# Bus_Terminal.net
KiCad netlist of a schematic drawn in Altium Designer
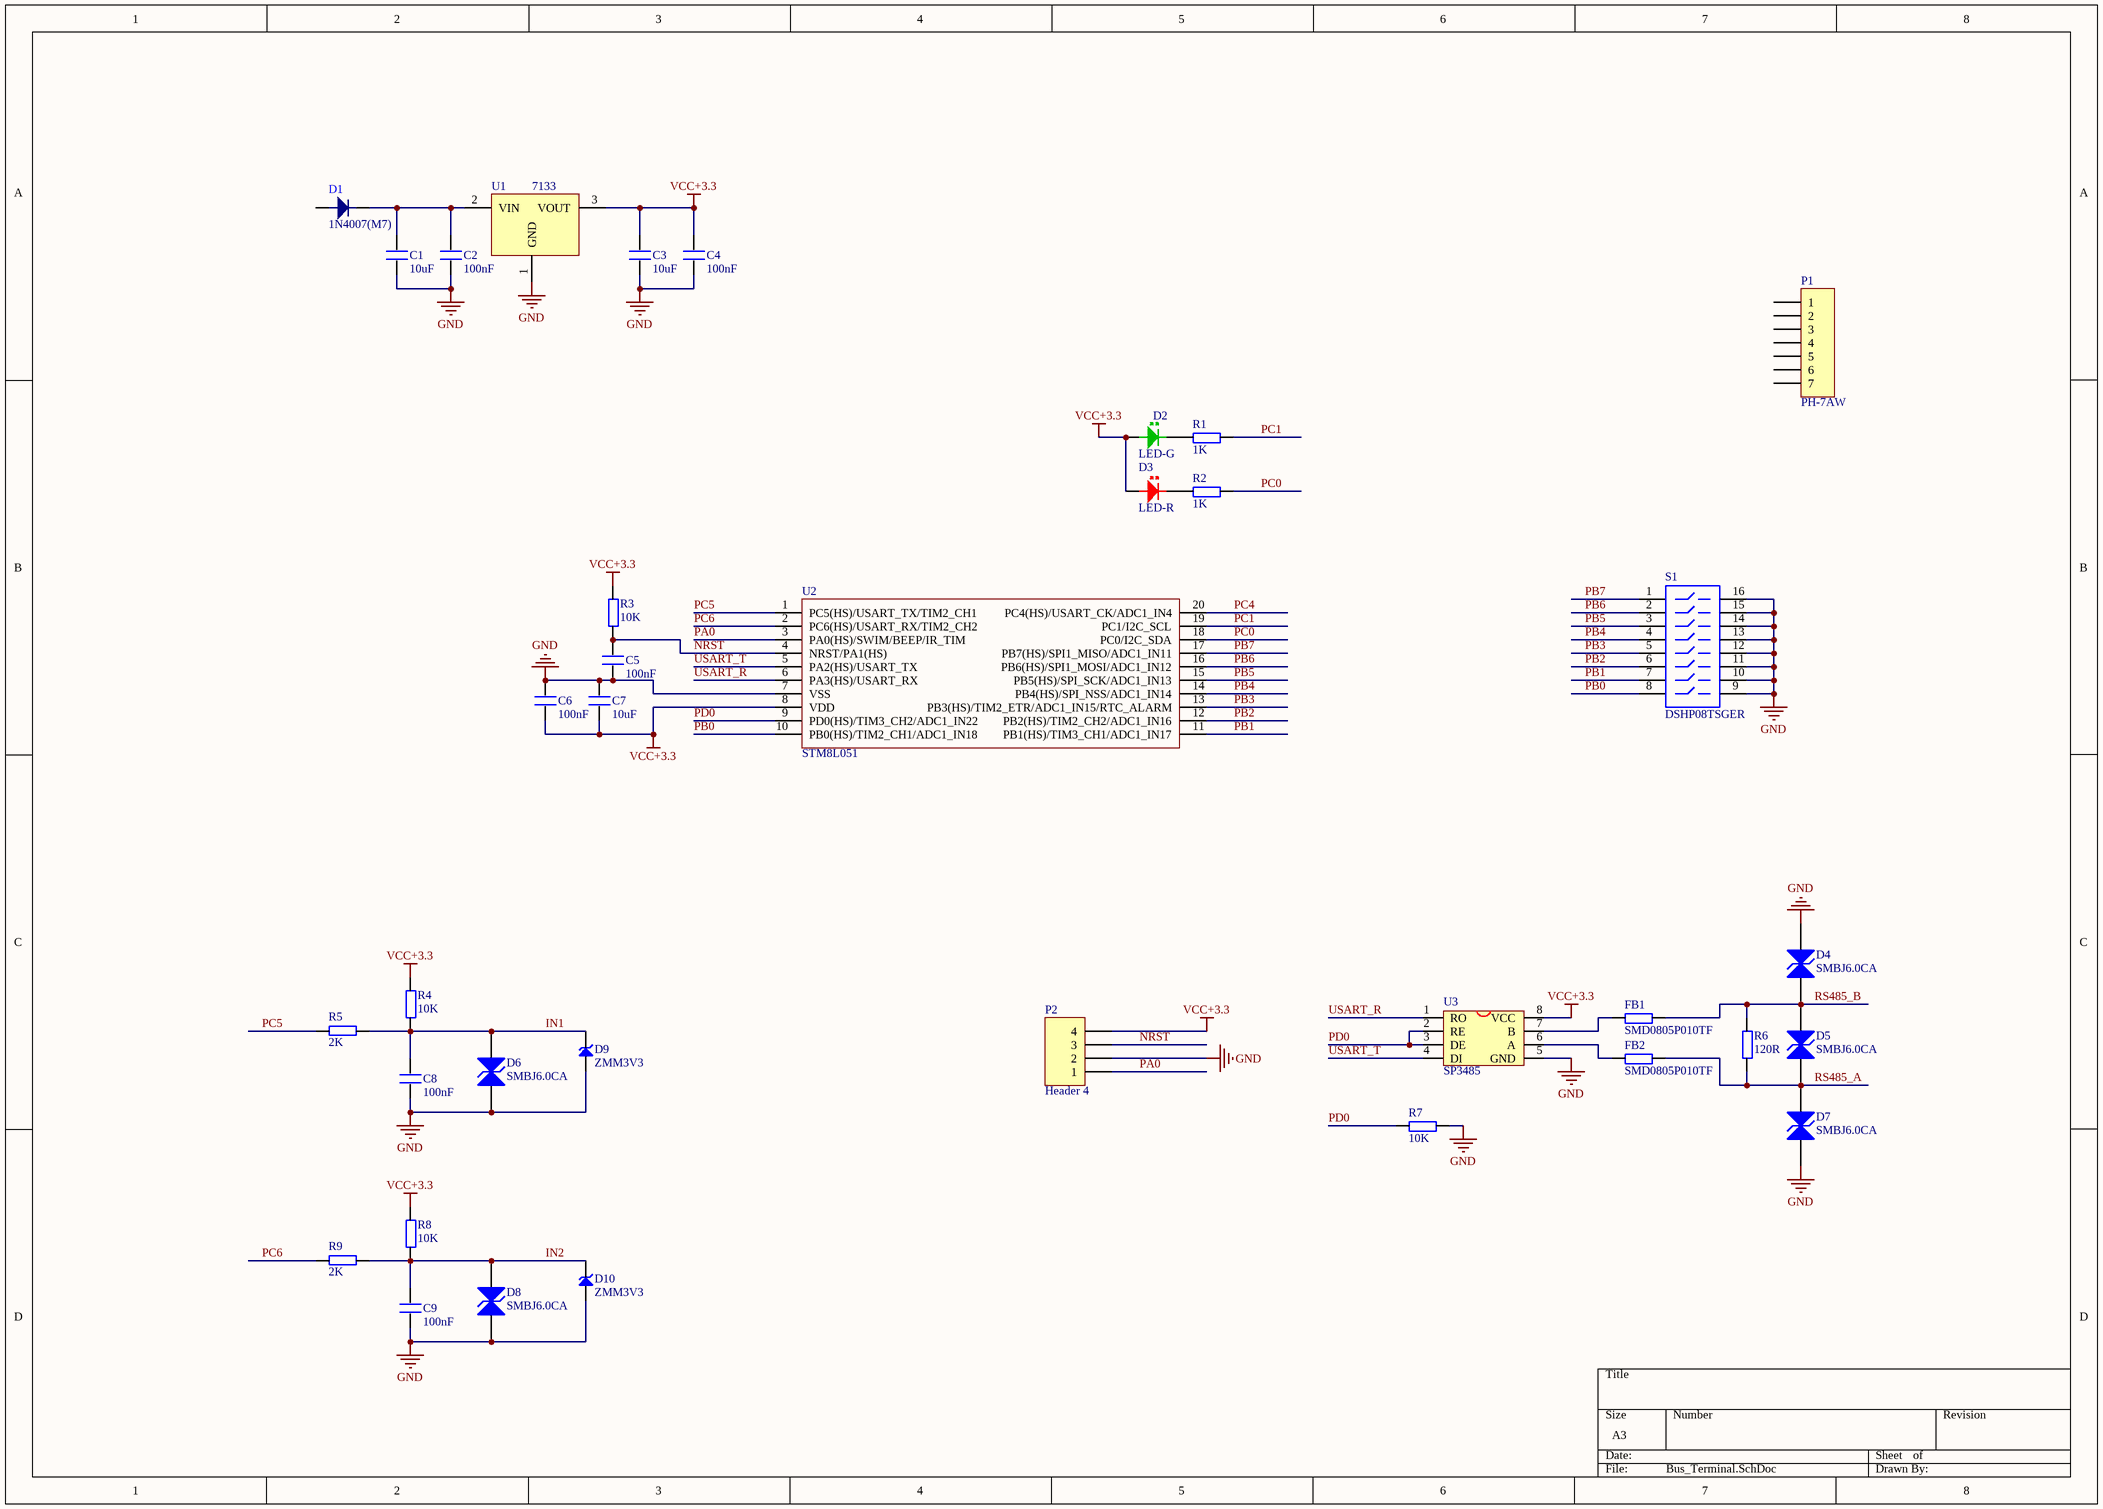
[diagram p0: Bus_Terminal.SchDoc]

(export (version "E")
  (design (tool "Eeschema 10.0.6"))
  (components
    (comp (ref "C1") (value "10uF") (footprint "0805-C") (libsource (lib "mylib") (part "C")))
    (comp (ref "C2") (value "100nF") (footprint "0603-C") (libsource (lib "mylib") (part "C")))
    (comp (ref "C3") (value "10uF") (footprint "0805-C") (libsource (lib "mylib") (part "C")))
    (comp (ref "C4") (value "100nF") (footprint "0603-C") (libsource (lib "mylib") (part "C")))
    (comp (ref "C5") (value "100nF") (footprint "0603-C") (libsource (lib "mylib") (part "C")))
    (comp (ref "C6") (value "100nF") (footprint "0603-C") (libsource (lib "mylib") (part "C")))
    (comp (ref "C7") (value "10uF") (footprint "0805-C") (libsource (lib "mylib") (part "C")))
    (comp (ref "C8") (value "100nF") (footprint "0603-C") (libsource (lib "mylib") (part "C")))
    (comp (ref "C9") (value "100nF") (footprint "0603-C") (libsource (lib "mylib") (part "C")))
    (comp (ref "D1")
      (value "1N4007(M7)")
      (footprint "DO-214AC(SMA)")
      (description "1A整流二极管")
      (libsource (lib "mylib") (part "1N4007"))
    )
    (comp (ref "D2")
      (value "LED-G")
      (footprint "0805-LED")
      (description "绿色LED")
      (libsource (lib "mylib") (part "LED-GRE"))
    )
    (comp (ref "D3")
      (value "LED-R")
      (footprint "0805-LED")
      (description "红色LED")
      (libsource (lib "mylib") (part "LED-RED"))
    )
    (comp (ref "D4")
      (value "SMBJ6.0CA")
      (footprint "SMB-DO-214AA-CA")
      (description "TVS")
      (libsource (lib "mylib") (part "SMBJ6.0CA"))
    )
    (comp (ref "D5")
      (value "SMBJ6.0CA")
      (footprint "SMB-DO-214AA-CA")
      (description "TVS")
      (libsource (lib "mylib") (part "SMBJ6.0CA"))
    )
    (comp (ref "D6")
      (value "SMBJ6.0CA")
      (footprint "SMB-DO-214AA-CA")
      (description "TVS")
      (libsource (lib "mylib") (part "SMBJ6.0CA"))
    )
    (comp (ref "D7")
      (value "SMBJ6.0CA")
      (footprint "SMB-DO-214AA-CA")
      (description "TVS")
      (libsource (lib "mylib") (part "SMBJ6.0CA"))
    )
    (comp (ref "D8")
      (value "SMBJ6.0CA")
      (footprint "SMB-DO-214AA-CA")
      (description "TVS")
      (libsource (lib "mylib") (part "SMBJ6.0CA"))
    )
    (comp (ref "D9") (value "ZMM3V3") (footprint "DIODE_ZMMx") (libsource (lib "mylib") (part "ZMM3V6")))
    (comp (ref "D10") (value "ZMM3V3") (footprint "DIODE_ZMMx") (libsource (lib "mylib") (part "ZMM3V6")))
    (comp (ref "FB1")
      (value "SMD0805P010TF")
      (footprint "0805-R")
      (description "保险丝")
      (libsource (lib "mylib") (part "Res"))
    )
    (comp (ref "FB2")
      (value "SMD0805P010TF")
      (footprint "0805-R")
      (description "保险丝")
      (libsource (lib "mylib") (part "Res"))
    )
    (comp (ref "P1")
      (value "PH-7AW")
      (footprint "PH-7AW")
      (description "连接器")
      (libsource (lib "mylib") (part "PH-7AW"))
    )
    (comp (ref "P2")
      (value "Header 4")
      (footprint "HDR1X4")
      (description "Header, 4-Pin")
      (fields (field (name "PUBLISHER") "Altium Limited"))
      (libsource (lib "mylib") (part "Header 4"))
    )
    (comp (ref "R1") (value "1K") (footprint "0603-R") (libsource (lib "mylib") (part "Res")))
    (comp (ref "R2") (value "1K") (footprint "0603-R") (libsource (lib "mylib") (part "Res")))
    (comp (ref "R3") (value "10K") (footprint "0603-R") (libsource (lib "mylib") (part "Res")))
    (comp (ref "R4") (value "10K") (footprint "0603-R") (libsource (lib "mylib") (part "Res")))
    (comp (ref "R5") (value "2K") (footprint "0603-R") (libsource (lib "mylib") (part "Res")))
    (comp (ref "R6") (value "120R") (footprint "0603-R") (libsource (lib "mylib") (part "Res")))
    (comp (ref "R7") (value "10K") (footprint "0603-R") (libsource (lib "mylib") (part "Res")))
    (comp (ref "R8") (value "10K") (footprint "0603-R") (libsource (lib "mylib") (part "Res")))
    (comp (ref "R9") (value "2K") (footprint "0603-R") (libsource (lib "mylib") (part "Res")))
    (comp (ref "S1")
      (value "DSHP08TSGER")
      (footprint "SOP127P890X230-16N")
      (description "贴片拨码开关")
      (libsource (lib "mylib") (part "DSHP08TSGER"))
    )
    (comp (ref "U1")
      (value "7133")
      (footprint "SOT-89")
      (description "LDO")
      (libsource (lib "mylib") (part "7133"))
    )
    (comp (ref "U2")
      (value "STM8L051")
      (footprint "TSSOP20")
      (description "单片机")
      (libsource (lib "mylib") (part "STM8L051"))
    )
    (comp (ref "U3") (value "SP3485") (footprint "SOP-8") (libsource (lib "mylib") (part "MAX3485")))
  )
  (nets
    (net (code "1") (name "/IN1") (class "Default")
      (node (ref "C8") (pin "2") (pintype "passive"))
      (node (ref "D6") (pin "2") (pinfunction "2_2") (pintype "passive"))
      (node (ref "D9") (pin "2") (pintype "passive"))
      (node (ref "R4") (pin "1") (pintype "passive"))
      (node (ref "R5") (pin "1") (pintype "passive"))
    )
    (net (code "2") (name "/IN2") (class "Default")
      (node (ref "C9") (pin "2") (pintype "passive"))
      (node (ref "D10") (pin "2") (pintype "passive"))
      (node (ref "D8") (pin "2") (pinfunction "2_2") (pintype "passive"))
      (node (ref "R8") (pin "1") (pintype "passive"))
      (node (ref "R9") (pin "1") (pintype "passive"))
    )
    (net (code "3") (name "/NRST") (class "Default")
      (node (ref "C5") (pin "2") (pintype "passive"))
      (node (ref "P2") (pin "3") (pinfunction "3_3") (pintype "passive"))
      (node (ref "R3") (pin "1") (pintype "passive"))
      (node (ref "U2") (pin "4") (pinfunction "NRST/PA1(HS)_4") (pintype "passive"))
    )
    (net (code "4") (name "/PA0") (class "Default")
      (node (ref "P2") (pin "1") (pinfunction "1_1") (pintype "passive"))
      (node (ref "U2") (pin "3") (pinfunction "PA0(HS)/SWIM/BEEP/IR_TIM_3") (pintype "passive"))
    )
    (net (code "5") (name "/PB0") (class "Default")
      (node (ref "S1") (pin "8") (pinfunction "8_8") (pintype "passive"))
      (node (ref "U2") (pin "10") (pinfunction "PB0(HS)/TIM2_CH1/ADC1_IN18_10") (pintype "passive"))
    )
    (net (code "6") (name "/PB1") (class "Default")
      (node (ref "S1") (pin "7") (pinfunction "7_7") (pintype "passive"))
      (node (ref "U2") (pin "11") (pinfunction "PB1(HS)/TIM3_CH1/ADC1_IN17_11") (pintype "passive"))
    )
    (net (code "7") (name "/PB2") (class "Default")
      (node (ref "S1") (pin "6") (pinfunction "6_6") (pintype "passive"))
      (node (ref "U2") (pin "12") (pinfunction "PB2(HS)/TIM2_CH2/ADC1_IN16_12") (pintype "passive"))
    )
    (net (code "8") (name "/PB3") (class "Default")
      (node (ref "S1") (pin "5") (pinfunction "5_5") (pintype "passive"))
      (node (ref "U2") (pin "13") (pinfunction "PB3(HS)/TIM2_ETR/ADC1_IN15/RTC_ALARM_13") (pintype "passive"))
    )
    (net (code "9") (name "/PB4") (class "Default")
      (node (ref "S1") (pin "4") (pinfunction "4_4") (pintype "passive"))
      (node (ref "U2") (pin "14") (pinfunction "PB4(HS)/SPI_NSS/ADC1_IN14_14") (pintype "passive"))
    )
    (net (code "10") (name "/PB5") (class "Default")
      (node (ref "S1") (pin "3") (pinfunction "3_3") (pintype "passive"))
      (node (ref "U2") (pin "15") (pinfunction "PB5(HS)/SPI_SCK/ADC1_IN13_15") (pintype "passive"))
    )
    (net (code "11") (name "/PB6") (class "Default")
      (node (ref "S1") (pin "2") (pinfunction "2_2") (pintype "passive"))
      (node (ref "U2") (pin "16") (pinfunction "PB6(HS)/SPI1_MOSI/ADC1_IN12_16") (pintype "passive"))
    )
    (net (code "12") (name "/PB7") (class "Default")
      (node (ref "S1") (pin "1") (pinfunction "1_1") (pintype "passive"))
      (node (ref "U2") (pin "17") (pinfunction "PB7(HS)/SPI1_MISO/ADC1_IN11_17") (pintype "passive"))
    )
    (net (code "13") (name "/PC0") (class "Default")
      (node (ref "R2") (pin "2") (pintype "passive"))
      (node (ref "U2") (pin "18") (pinfunction "PC0/I2C_SDA_18") (pintype "passive"))
    )
    (net (code "14") (name "/PC1") (class "Default")
      (node (ref "R1") (pin "2") (pintype "passive"))
      (node (ref "U2") (pin "19") (pinfunction "PC1/I2C_SCL_19") (pintype "passive"))
    )
    (net (code "15") (name "/PC4") (class "Default")
      (node (ref "U2") (pin "20") (pinfunction "PC4(HS)/USART_CK/ADC1_IN4_20") (pintype "passive"))
    )
    (net (code "16") (name "/PC5") (class "Default")
      (node (ref "R5") (pin "2") (pintype "passive"))
      (node (ref "U2") (pin "1") (pinfunction "PC5(HS)/USART_TX/TIM2_CH1_1") (pintype "passive"))
    )
    (net (code "17") (name "/PC6") (class "Default")
      (node (ref "R9") (pin "2") (pintype "passive"))
      (node (ref "U2") (pin "2") (pinfunction "PC6(HS)/USART_RX/TIM2_CH2_2") (pintype "passive"))
    )
    (net (code "18") (name "/PD0") (class "Default")
      (node (ref "R7") (pin "1") (pintype "passive"))
      (node (ref "U2") (pin "9") (pinfunction "PD0(HS)/TIM3_CH2/ADC1_IN22_9") (pintype "passive"))
      (node (ref "U3") (pin "2") (pinfunction "RE_2") (pintype "passive"))
      (node (ref "U3") (pin "3") (pinfunction "DE_3") (pintype "passive"))
    )
    (net (code "19") (name "/RS485_A") (class "Default")
      (node (ref "D5") (pin "1") (pinfunction "1_1") (pintype "passive"))
      (node (ref "D7") (pin "2") (pinfunction "2_2") (pintype "passive"))
      (node (ref "FB2") (pin "2") (pintype "passive"))
      (node (ref "R6") (pin "1") (pintype "passive"))
    )
    (net (code "20") (name "/RS485_B") (class "Default")
      (node (ref "D4") (pin "1") (pinfunction "1_1") (pintype "passive"))
      (node (ref "D5") (pin "2") (pinfunction "2_2") (pintype "passive"))
      (node (ref "FB1") (pin "2") (pintype "passive"))
      (node (ref "R6") (pin "2") (pintype "passive"))
    )
    (net (code "21") (name "/USART_R") (class "Default")
      (node (ref "U2") (pin "6") (pinfunction "PA3(HS)/USART_RX_6") (pintype "passive"))
      (node (ref "U3") (pin "1") (pinfunction "RO_1") (pintype "passive"))
    )
    (net (code "22") (name "/USART_T") (class "Default")
      (node (ref "U2") (pin "5") (pinfunction "PA2(HS)/USART_TX_5") (pintype "passive"))
      (node (ref "U3") (pin "4") (pinfunction "DI_4") (pintype "passive"))
    )
    (net (code "23") (name "GND") (class "Default")
      (node (ref "C1") (pin "1") (pintype "passive"))
      (node (ref "C2") (pin "1") (pintype "passive"))
      (node (ref "C3") (pin "1") (pintype "passive"))
      (node (ref "C4") (pin "1") (pintype "passive"))
      (node (ref "C5") (pin "1") (pintype "passive"))
      (node (ref "C6") (pin "2") (pintype "passive"))
      (node (ref "C7") (pin "2") (pintype "passive"))
      (node (ref "C8") (pin "1") (pintype "passive"))
      (node (ref "C9") (pin "1") (pintype "passive"))
      (node (ref "D10") (pin "1") (pintype "passive"))
      (node (ref "D4") (pin "2") (pinfunction "2_2") (pintype "passive"))
      (node (ref "D6") (pin "1") (pinfunction "1_1") (pintype "passive"))
      (node (ref "D7") (pin "1") (pinfunction "1_1") (pintype "passive"))
      (node (ref "D8") (pin "1") (pinfunction "1_1") (pintype "passive"))
      (node (ref "D9") (pin "1") (pintype "passive"))
      (node (ref "P2") (pin "2") (pinfunction "2_2") (pintype "passive"))
      (node (ref "R7") (pin "2") (pintype "passive"))
      (node (ref "S1") (pin "10") (pinfunction "10_10") (pintype "passive"))
      (node (ref "S1") (pin "11") (pinfunction "11_11") (pintype "passive"))
      (node (ref "S1") (pin "12") (pinfunction "12_12") (pintype "passive"))
      (node (ref "S1") (pin "13") (pinfunction "13_13") (pintype "passive"))
      (node (ref "S1") (pin "14") (pinfunction "14_14") (pintype "passive"))
      (node (ref "S1") (pin "15") (pinfunction "15_15") (pintype "passive"))
      (node (ref "S1") (pin "16") (pinfunction "16_16") (pintype "passive"))
      (node (ref "S1") (pin "9") (pinfunction "9_9") (pintype "passive"))
      (node (ref "U1") (pin "1") (pinfunction "GND_1") (pintype "passive"))
      (node (ref "U2") (pin "7") (pinfunction "VSS_7") (pintype "passive"))
      (node (ref "U3") (pin "5") (pinfunction "GND_5") (pintype "passive"))
    )
    (net (code "24") (name "Net-(D2-Pad2)") (class "Default")
      (node (ref "D2") (pin "2") (pintype "passive"))
      (node (ref "R1") (pin "1") (pintype "passive"))
    )
    (net (code "25") (name "Net-(D3-Pad2)") (class "Default")
      (node (ref "D3") (pin "2") (pintype "passive"))
      (node (ref "R2") (pin "1") (pintype "passive"))
    )
    (net (code "26") (name "Net-(U1-VIN)") (class "Default")
      (node (ref "C1") (pin "2") (pintype "passive"))
      (node (ref "C2") (pin "2") (pintype "passive"))
      (node (ref "D1") (pin "2") (pintype "passive"))
      (node (ref "U1") (pin "2") (pinfunction "VIN_2") (pintype "passive"))
    )
    (net (code "27") (name "Net-(U3-A)") (class "Default")
      (node (ref "FB2") (pin "1") (pintype "passive"))
      (node (ref "U3") (pin "6") (pinfunction "A_6") (pintype "passive"))
    )
    (net (code "28") (name "Net-(U3-B)") (class "Default")
      (node (ref "FB1") (pin "1") (pintype "passive"))
      (node (ref "U3") (pin "7") (pinfunction "B_7") (pintype "passive"))
    )
    (net (code "29") (name "VCC+3.3") (class "Default")
      (node (ref "C3") (pin "2") (pintype "passive"))
      (node (ref "C4") (pin "2") (pintype "passive"))
      (node (ref "C6") (pin "1") (pintype "passive"))
      (node (ref "C7") (pin "1") (pintype "passive"))
      (node (ref "D2") (pin "1") (pintype "passive"))
      (node (ref "D3") (pin "1") (pintype "passive"))
      (node (ref "P2") (pin "4") (pinfunction "4_4") (pintype "passive"))
      (node (ref "R3") (pin "2") (pintype "passive"))
      (node (ref "R4") (pin "2") (pintype "passive"))
      (node (ref "R8") (pin "2") (pintype "passive"))
      (node (ref "U1") (pin "3") (pinfunction "VOUT_3") (pintype "passive"))
      (node (ref "U2") (pin "8") (pinfunction "VDD_8") (pintype "passive"))
      (node (ref "U3") (pin "8") (pinfunction "VCC_8") (pintype "passive"))
    )
    (net (code "30") (name "unconnected-(D1-Pad1)") (class "Default")
      (node (ref "D1") (pin "1") (pintype "passive"))
    )
    (net (code "31") (name "unconnected-(P1-Pad1)") (class "Default")
      (node (ref "P1") (pin "1") (pinfunction "1_1") (pintype "passive"))
    )
    (net (code "32") (name "unconnected-(P1-Pad2)") (class "Default")
      (node (ref "P1") (pin "2") (pinfunction "2_2") (pintype "passive"))
    )
    (net (code "33") (name "unconnected-(P1-Pad3)") (class "Default")
      (node (ref "P1") (pin "3") (pinfunction "3_3") (pintype "passive"))
    )
    (net (code "34") (name "unconnected-(P1-Pad4)") (class "Default")
      (node (ref "P1") (pin "4") (pinfunction "4_4") (pintype "passive"))
    )
    (net (code "35") (name "unconnected-(P1-Pad5)") (class "Default")
      (node (ref "P1") (pin "5") (pinfunction "5_5") (pintype "passive"))
    )
    (net (code "36") (name "unconnected-(P1-Pad6)") (class "Default")
      (node (ref "P1") (pin "6") (pinfunction "6_6") (pintype "passive"))
    )
    (net (code "37") (name "unconnected-(P1-Pad7)") (class "Default")
      (node (ref "P1") (pin "7") (pinfunction "7_7") (pintype "passive"))
    )
  )
)
